# US.net
KiCad netlist of a schematic drawn in EAGLE
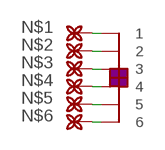
[diagram p0: schematic, sheet 1]

(export (version "E")
  (design (tool "Eeschema 10.0.6"))
  (components
    (comp (ref "C1")
      (value "6P6C_FEMALESMD")
      (footprint "eagle-import:6P6C_FEMALE")
      (libsource (lib "eagle-import") (part "6P6C_FEMALESMD"))
    )
    (comp (ref "PAD1")
      (value "BETTERPAD_2.54")
      (footprint "eagle-import:SUPERIORSIM")
      (libsource (lib "eagle-import") (part "BETTERPAD_2.54"))
    )
    (comp (ref "PAD2")
      (value "BETTERPAD_2.54")
      (footprint "eagle-import:SUPERIORSIM")
      (libsource (lib "eagle-import") (part "BETTERPAD_2.54"))
    )
    (comp (ref "PAD3")
      (value "BETTERPAD_2.54")
      (footprint "eagle-import:SUPERIORSIM")
      (libsource (lib "eagle-import") (part "BETTERPAD_2.54"))
    )
    (comp (ref "PAD4")
      (value "BETTERPAD_2.54")
      (footprint "eagle-import:SUPERIORSIM")
      (libsource (lib "eagle-import") (part "BETTERPAD_2.54"))
    )
    (comp (ref "PAD5")
      (value "BETTERPAD_2.54")
      (footprint "eagle-import:SUPERIORSIM")
      (libsource (lib "eagle-import") (part "BETTERPAD_2.54"))
    )
    (comp (ref "PAD6")
      (value "BETTERPAD_2.54")
      (footprint "eagle-import:SUPERIORSIM")
      (libsource (lib "eagle-import") (part "BETTERPAD_2.54"))
    )
  )
  (nets
    (net (code "1") (name "/N$1") (class "Default")
      (node (ref "C1") (pin "1") (pinfunction "1_1") (pintype "bidirectional"))
      (node (ref "PAD1") (pin ".") (pinfunction "P_.") (pintype "passive"))
    )
    (net (code "2") (name "/N$2") (class "Default")
      (node (ref "C1") (pin "2") (pinfunction "2_2") (pintype "bidirectional"))
      (node (ref "PAD2") (pin ".") (pinfunction "P_.") (pintype "passive"))
    )
    (net (code "3") (name "/N$3") (class "Default")
      (node (ref "C1") (pin "3") (pinfunction "3_3") (pintype "bidirectional"))
      (node (ref "PAD3") (pin ".") (pinfunction "P_.") (pintype "passive"))
    )
    (net (code "4") (name "/N$4") (class "Default")
      (node (ref "C1") (pin "4") (pinfunction "4_4") (pintype "bidirectional"))
      (node (ref "PAD4") (pin ".") (pinfunction "P_.") (pintype "passive"))
    )
    (net (code "5") (name "/N$5") (class "Default")
      (node (ref "C1") (pin "5") (pinfunction "5_5") (pintype "bidirectional"))
      (node (ref "PAD5") (pin ".") (pinfunction "P_.") (pintype "passive"))
    )
    (net (code "6") (name "/N$6") (class "Default")
      (node (ref "C1") (pin "6") (pinfunction "6_6") (pintype "bidirectional"))
      (node (ref "PAD6") (pin ".") (pinfunction "P_.") (pintype "passive"))
    )
  )
)
